# valve_driver_pwm_ctrl.net
KiCad netlist of a schematic drawn in EAGLE
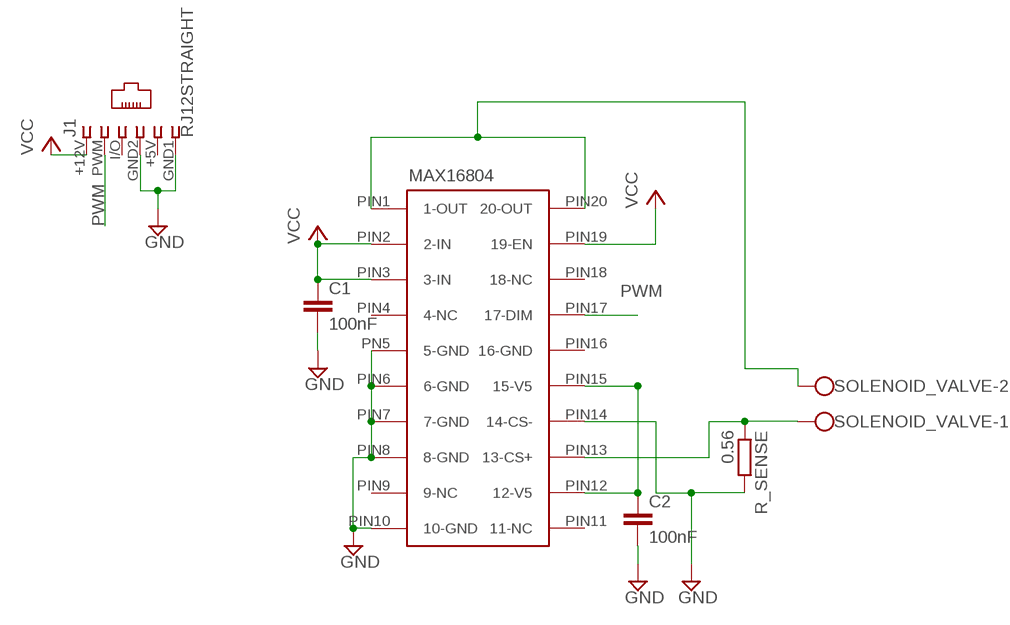
[diagram p0: schematic, sheet 1]

(export (version "E")
  (design (tool "Eeschema 10.0.6"))
  (components
    (comp (ref "C1")
      (value "100nF")
      (footprint "eagle-import:C1206")
      (libsource (lib "eagle-import") (part "C-EUC1206"))
    )
    (comp (ref "C2")
      (value "100nF")
      (footprint "eagle-import:C1206")
      (libsource (lib "eagle-import") (part "C-EUC1206"))
    )
    (comp (ref "J1")
      (value "RJ12STRAIGHT")
      (footprint "eagle-import:RJ12-STRAIGHT")
      (libsource (lib "eagle-import") (part "RJ12STRAIGHT"))
    )
    (comp (ref "R_SENSE")
      (value "0.56")
      (footprint "eagle-import:M1206")
      (libsource (lib "eagle-import") (part "R-EU_M1206"))
    )
    (comp (ref "SOLENOID_VALVE")
      (value "W237-102")
      (footprint "eagle-import:W237-102")
      (fields (field (name "MPN") "237-102"))
      (libsource (lib "eagle-import") (part "W237-102"))
    )
    (comp (ref "U$1")
      (value "MAX16804ATP+")
      (footprint "eagle-import:TQFN-20")
      (libsource (lib "eagle-import") (part "MAX16804ATP+"))
    )
  )
  (nets
    (net (code "1") (name "/PWM") (class "Default")
      (node (ref "J1") (pin "PWM") (pinfunction "2_PWM") (pintype "bidirectional"))
      (node (ref "U$1") (pin "PIN17") (pinfunction "17-DIM_PIN17") (pintype "bidirectional"))
    )
    (net (code "2") (name "GND") (class "Default")
      (node (ref "C1") (pin "2") (pinfunction "2_2") (pintype "passive"))
      (node (ref "C2") (pin "2") (pinfunction "2_2") (pintype "passive"))
      (node (ref "J1") (pin "GND1") (pinfunction "6_GND1") (pintype "bidirectional"))
      (node (ref "J1") (pin "GND2") (pinfunction "4_GND2") (pintype "bidirectional"))
      (node (ref "R_SENSE") (pin "2") (pinfunction "2_2") (pintype "passive"))
      (node (ref "U$1") (pin "PIN10") (pinfunction "10-GND_PIN10") (pintype "bidirectional"))
      (node (ref "U$1") (pin "PIN14") (pinfunction "14-CS-_PIN14") (pintype "bidirectional"))
      (node (ref "U$1") (pin "PIN6") (pinfunction "6-GND_PIN6") (pintype "bidirectional"))
      (node (ref "U$1") (pin "PIN7") (pinfunction "7-GND_PIN7") (pintype "bidirectional"))
      (node (ref "U$1") (pin "PIN8") (pinfunction "8-GND_PIN8") (pintype "bidirectional"))
      (node (ref "U$1") (pin "PN5") (pinfunction "5-GND_PN5") (pintype "bidirectional"))
    )
    (net (code "3") (name "Net-(SOLENOID_VALVEA-KL)") (class "Default")
      (node (ref "R_SENSE") (pin "1") (pinfunction "1_1") (pintype "passive"))
      (node (ref "SOLENOID_VALVE") (pin "1") (pinfunction "KL_1") (pintype "passive"))
      (node (ref "U$1") (pin "PIN13") (pinfunction "13-CS+_PIN13") (pintype "bidirectional"))
    )
    (net (code "4") (name "Net-(SOLENOID_VALVEB-KL)") (class "Default")
      (node (ref "SOLENOID_VALVE") (pin "2") (pinfunction "KL_2") (pintype "passive"))
      (node (ref "U$1") (pin "PIN1") (pinfunction "1-OUT_PIN1") (pintype "bidirectional"))
      (node (ref "U$1") (pin "PIN20") (pinfunction "20-OUT_PIN20") (pintype "bidirectional"))
    )
    (net (code "5") (name "Net-(U$1-12-V5)") (class "Default")
      (node (ref "C2") (pin "1") (pinfunction "1_1") (pintype "passive"))
      (node (ref "U$1") (pin "PIN12") (pinfunction "12-V5_PIN12") (pintype "bidirectional"))
      (node (ref "U$1") (pin "PIN15") (pinfunction "15-V5_PIN15") (pintype "bidirectional"))
    )
    (net (code "6") (name "VCC") (class "Default")
      (node (ref "C1") (pin "1") (pinfunction "1_1") (pintype "passive"))
      (node (ref "J1") (pin "+12V") (pinfunction "1_+12V") (pintype "bidirectional"))
      (node (ref "U$1") (pin "PIN19") (pinfunction "19-EN_PIN19") (pintype "bidirectional"))
      (node (ref "U$1") (pin "PIN2") (pinfunction "2-IN_PIN2") (pintype "bidirectional"))
      (node (ref "U$1") (pin "PIN3") (pinfunction "3-IN_PIN3") (pintype "bidirectional"))
    )
    (net (code "7") (name "unconnected-(J1-3-PadI{slash}O)") (class "Default")
      (node (ref "J1") (pin "I/O") (pinfunction "3_I/O") (pintype "bidirectional"))
    )
    (net (code "8") (name "unconnected-(J1-5-Pad+5V)") (class "Default")
      (node (ref "J1") (pin "+5V") (pinfunction "5_+5V") (pintype "bidirectional"))
    )
    (net (code "9") (name "unconnected-(U$1-4-NC-PadPIN4)") (class "Default")
      (node (ref "U$1") (pin "PIN4") (pinfunction "4-NC_PIN4") (pintype "bidirectional"))
    )
    (net (code "10") (name "unconnected-(U$1-9-NC-PadPIN9)") (class "Default")
      (node (ref "U$1") (pin "PIN9") (pinfunction "9-NC_PIN9") (pintype "bidirectional"))
    )
    (net (code "11") (name "unconnected-(U$1-11-NC-PadPIN11)") (class "Default")
      (node (ref "U$1") (pin "PIN11") (pinfunction "11-NC_PIN11") (pintype "bidirectional"))
    )
    (net (code "12") (name "unconnected-(U$1-16-GND-PadPIN16)") (class "Default")
      (node (ref "U$1") (pin "PIN16") (pinfunction "16-GND_PIN16") (pintype "bidirectional"))
    )
    (net (code "13") (name "unconnected-(U$1-18-NC-PadPIN18)") (class "Default")
      (node (ref "U$1") (pin "PIN18") (pinfunction "18-NC_PIN18") (pintype "bidirectional"))
    )
  )
)
